# QCopterRC_KEY_Sch.net
KiCad netlist of a schematic drawn in Altium Designer
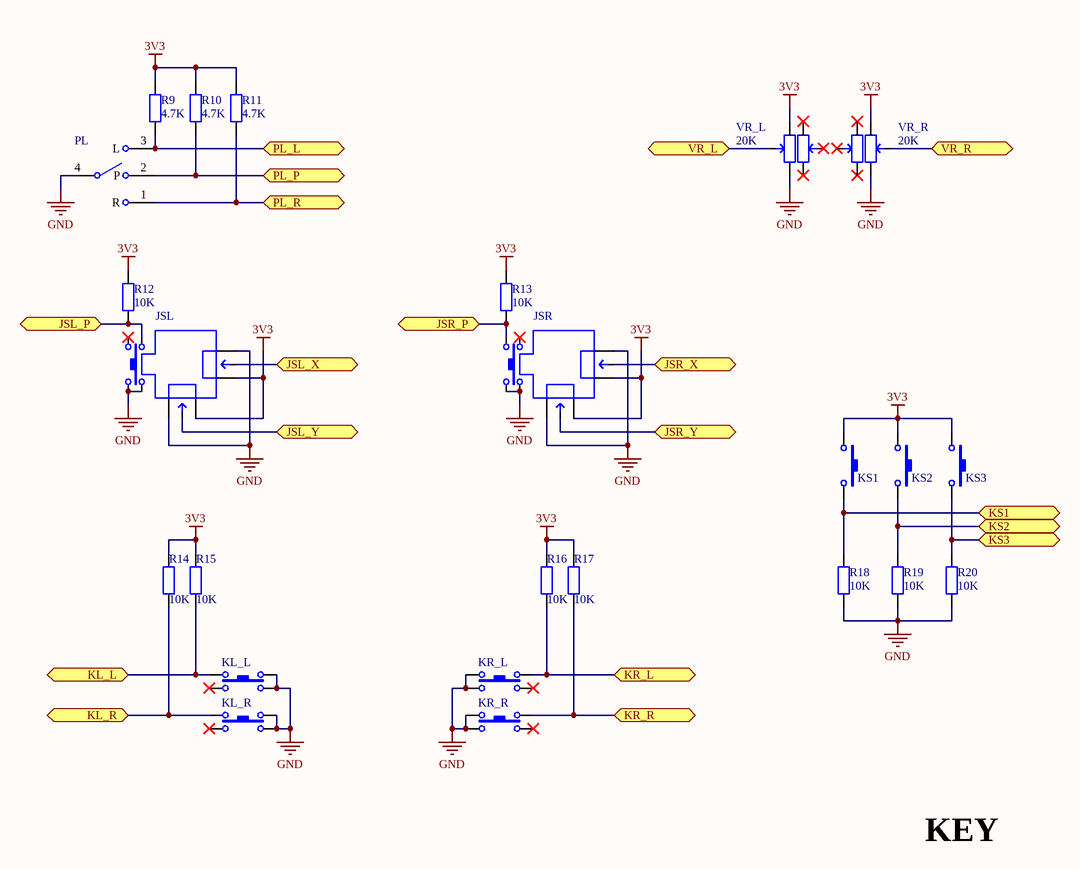
[diagram p0: QCopterRC_KEY_Sch.SchDoc]

(export (version "E")
  (design (tool "Eeschema 10.0.6"))
  (components
    (comp (ref "JSL")
      (value "JoyStick")
      (footprint "PCB_Switch:JoyStick")
      (libsource (lib "SCH_Switch") (part "JoyStick"))
    )
    (comp (ref "JSR")
      (value "JoyStick")
      (footprint "PCB_Switch:JoyStick")
      (libsource (lib "SCH_Switch") (part "JoyStick"))
    )
    (comp (ref "KL_L")
      (value "BT_TACT_12X12_D180")
      (footprint "PCB_Switch:BT_TACT_12X12_D180")
      (description "Switch")
      (libsource (lib "SCH_Switch") (part "BT_TACT_12X12_D180"))
    )
    (comp (ref "KL_R")
      (value "BT_TACT_12X12_D180")
      (footprint "PCB_Switch:BT_TACT_12X12_D180")
      (description "Switch")
      (libsource (lib "SCH_Switch") (part "BT_TACT_12X12_D180"))
    )
    (comp (ref "KR_L")
      (value "BT_TACT_12X12_D180")
      (footprint "PCB_Switch:BT_TACT_12X12_D180")
      (description "Switch")
      (libsource (lib "SCH_Switch") (part "BT_TACT_12X12_D180"))
    )
    (comp (ref "KR_R")
      (value "BT_TACT_12X12_D180")
      (footprint "PCB_Switch:BT_TACT_12X12_D180")
      (description "Switch")
      (libsource (lib "SCH_Switch") (part "BT_TACT_12X12_D180"))
    )
    (comp (ref "KS1")
      (value "BT_TACT_3x6_180")
      (footprint "PCB_Switch:BT_TACT_3x6_180")
      (description "Switch")
      (libsource (lib "SCH_Switch") (part "BT_TACT_3x6_180"))
    )
    (comp (ref "KS2")
      (value "BT_TACT_3x6_180")
      (footprint "PCB_Switch:BT_TACT_3x6_180")
      (description "Switch")
      (libsource (lib "SCH_Switch") (part "BT_TACT_3x6_180"))
    )
    (comp (ref "KS3")
      (value "BT_TACT_3x6_180")
      (footprint "PCB_Switch:BT_TACT_3x6_180")
      (description "Switch")
      (libsource (lib "SCH_Switch") (part "BT_TACT_3x6_180"))
    )
    (comp (ref "PL")
      (value "BT_PushLever_11*12_90")
      (footprint "PCB_Switch:BT_PushLever_11*12_90")
      (description "Switch")
      (libsource (lib "SCH_Switch") (part "BT_PushLever_11*12_90"))
    )
    (comp (ref "R9")
      (value "4.7K")
      (footprint "PCB_Passive:RES_0603")
      (description "Resistor")
      (fields (field (name "Comment") "Res_0603"))
      (libsource (lib "SCH_Passive") (part "Res_0603"))
    )
    (comp (ref "R10")
      (value "4.7K")
      (footprint "PCB_Passive:RES_0603")
      (description "Resistor")
      (fields (field (name "Comment") "Res_0603"))
      (libsource (lib "SCH_Passive") (part "Res_0603"))
    )
    (comp (ref "R11")
      (value "4.7K")
      (footprint "PCB_Passive:RES_0603")
      (description "Resistor")
      (fields (field (name "Comment") "Res_0603"))
      (libsource (lib "SCH_Passive") (part "Res_0603"))
    )
    (comp (ref "R12")
      (value "10K")
      (footprint "PCB_Passive:RES_0603")
      (description "Resistor")
      (fields (field (name "Comment") "Res_0603"))
      (libsource (lib "SCH_Passive") (part "Res_0603"))
    )
    (comp (ref "R13")
      (value "10K")
      (footprint "PCB_Passive:RES_0603")
      (description "Resistor")
      (fields (field (name "Comment") "Res_0603"))
      (libsource (lib "SCH_Passive") (part "Res_0603"))
    )
    (comp (ref "R14")
      (value "10K")
      (footprint "PCB_Passive:RES_0603")
      (description "Resistor")
      (fields (field (name "Comment") "Res_0603"))
      (libsource (lib "SCH_Passive") (part "Res_0603"))
    )
    (comp (ref "R15")
      (value "10K")
      (footprint "PCB_Passive:RES_0603")
      (description "Resistor")
      (fields (field (name "Comment") "Res_0603"))
      (libsource (lib "SCH_Passive") (part "Res_0603"))
    )
    (comp (ref "R16")
      (value "10K")
      (footprint "PCB_Passive:RES_0603")
      (description "Resistor")
      (fields (field (name "Comment") "Res_0603"))
      (libsource (lib "SCH_Passive") (part "Res_0603"))
    )
    (comp (ref "R17")
      (value "10K")
      (footprint "PCB_Passive:RES_0603")
      (description "Resistor")
      (fields (field (name "Comment") "Res_0603"))
      (libsource (lib "SCH_Passive") (part "Res_0603"))
    )
    (comp (ref "R18")
      (value "10K")
      (footprint "PCB_Passive:RES_0603")
      (description "Resistor")
      (fields (field (name "Comment") "Res_0603"))
      (libsource (lib "SCH_Passive") (part "Res_0603"))
    )
    (comp (ref "R19")
      (value "10K")
      (footprint "PCB_Passive:RES_0603")
      (description "Resistor")
      (fields (field (name "Comment") "Res_0603"))
      (libsource (lib "SCH_Passive") (part "Res_0603"))
    )
    (comp (ref "R20")
      (value "10K")
      (footprint "PCB_Passive:RES_0603")
      (description "Resistor")
      (fields (field (name "Comment") "Res_0603"))
      (libsource (lib "SCH_Passive") (part "Res_0603"))
    )
    (comp (ref "VR_L")
      (value "20K")
      (footprint "PCB_Passive:RES_45MM_DIP")
      (description "Resistor")
      (fields (field (name "Comment") "RES_45MM_DIP"))
      (libsource (lib "SCH_Passive") (part "RES_45MM_DIP"))
    )
    (comp (ref "VR_R")
      (value "20K")
      (footprint "PCB_Passive:RES_45MM_DIP")
      (description "Resistor")
      (fields (field (name "Comment") "RES_45MM_DIP"))
      (libsource (lib "SCH_Passive") (part "RES_45MM_DIP"))
    )
  )
  (nets
    (net (code "1") (name "/JSL_P") (class "Default")
      (node (ref "JSL") (pin "9") (pinfunction "9_9") (pintype "passive"))
      (node (ref "R12") (pin "2") (pinfunction "2_2") (pintype "passive"))
    )
    (net (code "2") (name "/JSL_X") (class "Default")
      (node (ref "JSL") (pin "5") (pinfunction "5_5") (pintype "passive"))
    )
    (net (code "3") (name "/JSL_Y") (class "Default")
      (node (ref "JSL") (pin "2") (pinfunction "2_2") (pintype "passive"))
    )
    (net (code "4") (name "/JSR_P") (class "Default")
      (node (ref "JSR") (pin "7") (pinfunction "7_7") (pintype "passive"))
      (node (ref "R13") (pin "2") (pinfunction "2_2") (pintype "passive"))
    )
    (net (code "5") (name "/JSR_X") (class "Default")
      (node (ref "JSR") (pin "5") (pinfunction "5_5") (pintype "passive"))
    )
    (net (code "6") (name "/JSR_Y") (class "Default")
      (node (ref "JSR") (pin "2") (pinfunction "2_2") (pintype "passive"))
    )
    (net (code "7") (name "/KL_L") (class "Default")
      (node (ref "KL_L") (pin "1") (pinfunction "1_1") (pintype "passive"))
      (node (ref "R15") (pin "2") (pinfunction "2_2") (pintype "passive"))
    )
    (net (code "8") (name "/KL_R") (class "Default")
      (node (ref "KL_R") (pin "1") (pinfunction "1_1") (pintype "passive"))
      (node (ref "R14") (pin "2") (pinfunction "2_2") (pintype "passive"))
    )
    (net (code "9") (name "/KR_L") (class "Default")
      (node (ref "KR_L") (pin "2") (pinfunction "2_2") (pintype "passive"))
      (node (ref "R16") (pin "2") (pinfunction "2_2") (pintype "passive"))
    )
    (net (code "10") (name "/KR_R") (class "Default")
      (node (ref "KR_R") (pin "2") (pinfunction "2_2") (pintype "passive"))
      (node (ref "R17") (pin "2") (pinfunction "2_2") (pintype "passive"))
    )
    (net (code "11") (name "/KS1") (class "Default")
      (node (ref "KS1") (pin "2") (pinfunction "2_2") (pintype "passive"))
      (node (ref "R18") (pin "1") (pinfunction "1_1") (pintype "passive"))
    )
    (net (code "12") (name "/KS2") (class "Default")
      (node (ref "KS2") (pin "2") (pinfunction "2_2") (pintype "passive"))
      (node (ref "R19") (pin "1") (pinfunction "1_1") (pintype "passive"))
    )
    (net (code "13") (name "/KS3") (class "Default")
      (node (ref "KS3") (pin "2") (pinfunction "2_2") (pintype "passive"))
      (node (ref "R20") (pin "1") (pinfunction "1_1") (pintype "passive"))
    )
    (net (code "14") (name "/PL_L") (class "Default")
      (node (ref "PL") (pin "3") (pinfunction "L_3") (pintype "passive"))
      (node (ref "R9") (pin "2") (pinfunction "2_2") (pintype "passive"))
    )
    (net (code "15") (name "/PL_P") (class "Default")
      (node (ref "PL") (pin "2") (pinfunction "P_2") (pintype "passive"))
      (node (ref "R10") (pin "2") (pinfunction "2_2") (pintype "passive"))
    )
    (net (code "16") (name "/PL_R") (class "Default")
      (node (ref "PL") (pin "1") (pinfunction "R_1") (pintype "passive"))
      (node (ref "R11") (pin "2") (pinfunction "2_2") (pintype "passive"))
    )
    (net (code "17") (name "/VR_L") (class "Default")
      (node (ref "VR_L") (pin "2") (pinfunction "W_2") (pintype "passive"))
    )
    (net (code "18") (name "/VR_R") (class "Default")
      (node (ref "VR_R") (pin "4") (pinfunction "W_4") (pintype "passive"))
    )
    (net (code "19") (name "3V3") (class "Default")
      (node (ref "JSL") (pin "3") (pinfunction "3_3") (pintype "passive"))
      (node (ref "JSL") (pin "4") (pinfunction "4_4") (pintype "passive"))
      (node (ref "JSR") (pin "3") (pinfunction "3_3") (pintype "passive"))
      (node (ref "JSR") (pin "4") (pinfunction "4_4") (pintype "passive"))
      (node (ref "KS1") (pin "1") (pinfunction "1_1") (pintype "passive"))
      (node (ref "KS2") (pin "1") (pinfunction "1_1") (pintype "passive"))
      (node (ref "KS3") (pin "1") (pinfunction "1_1") (pintype "passive"))
      (node (ref "R10") (pin "1") (pinfunction "1_1") (pintype "passive"))
      (node (ref "R11") (pin "1") (pinfunction "1_1") (pintype "passive"))
      (node (ref "R12") (pin "1") (pinfunction "1_1") (pintype "passive"))
      (node (ref "R13") (pin "1") (pinfunction "1_1") (pintype "passive"))
      (node (ref "R14") (pin "1") (pinfunction "1_1") (pintype "passive"))
      (node (ref "R15") (pin "1") (pinfunction "1_1") (pintype "passive"))
      (node (ref "R16") (pin "1") (pinfunction "1_1") (pintype "passive"))
      (node (ref "R17") (pin "1") (pinfunction "1_1") (pintype "passive"))
      (node (ref "R9") (pin "1") (pinfunction "1_1") (pintype "passive"))
      (node (ref "VR_L") (pin "1") (pinfunction "U_1") (pintype "passive"))
      (node (ref "VR_R") (pin "3") (pinfunction "U_3") (pintype "passive"))
    )
    (net (code "20") (name "GND") (class "Default")
      (node (ref "JSL") (pin "1") (pinfunction "1_1") (pintype "passive"))
      (node (ref "JSL") (pin "10") (pinfunction "10_10") (pintype "passive"))
      (node (ref "JSL") (pin "6") (pinfunction "6_6") (pintype "passive"))
      (node (ref "JSL") (pin "8") (pinfunction "8_8") (pintype "passive"))
      (node (ref "JSR") (pin "1") (pinfunction "1_1") (pintype "passive"))
      (node (ref "JSR") (pin "10") (pinfunction "10_10") (pintype "passive"))
      (node (ref "JSR") (pin "6") (pinfunction "6_6") (pintype "passive"))
      (node (ref "JSR") (pin "8") (pinfunction "8_8") (pintype "passive"))
      (node (ref "KL_L") (pin "2") (pinfunction "2_2") (pintype "passive"))
      (node (ref "KL_L") (pin "4") (pinfunction "4_4") (pintype "passive"))
      (node (ref "KL_R") (pin "2") (pinfunction "2_2") (pintype "passive"))
      (node (ref "KL_R") (pin "4") (pinfunction "4_4") (pintype "passive"))
      (node (ref "KR_L") (pin "1") (pinfunction "1_1") (pintype "passive"))
      (node (ref "KR_L") (pin "3") (pinfunction "3_3") (pintype "passive"))
      (node (ref "KR_R") (pin "1") (pinfunction "1_1") (pintype "passive"))
      (node (ref "KR_R") (pin "3") (pinfunction "3_3") (pintype "passive"))
      (node (ref "PL") (pin "4") (pinfunction "4_4") (pintype "passive"))
      (node (ref "R18") (pin "2") (pinfunction "2_2") (pintype "passive"))
      (node (ref "R19") (pin "2") (pinfunction "2_2") (pintype "passive"))
      (node (ref "R20") (pin "2") (pinfunction "2_2") (pintype "passive"))
      (node (ref "VR_L") (pin "5") (pinfunction "D_5") (pintype "passive"))
      (node (ref "VR_R") (pin "6") (pinfunction "D_6") (pintype "passive"))
    )
    (net (code "21") (name "unconnected-(JSL-Pad7)") (class "Default")
      (node (ref "JSL") (pin "7") (pinfunction "7_7") (pintype "passive+no_connect"))
    )
    (net (code "22") (name "unconnected-(JSR-Pad9)") (class "Default")
      (node (ref "JSR") (pin "9") (pinfunction "9_9") (pintype "passive+no_connect"))
    )
    (net (code "23") (name "unconnected-(KL_L-Pad3)") (class "Default")
      (node (ref "KL_L") (pin "3") (pinfunction "3_3") (pintype "passive+no_connect"))
    )
    (net (code "24") (name "unconnected-(KL_R-Pad3)") (class "Default")
      (node (ref "KL_R") (pin "3") (pinfunction "3_3") (pintype "passive+no_connect"))
    )
    (net (code "25") (name "unconnected-(KR_L-Pad4)") (class "Default")
      (node (ref "KR_L") (pin "4") (pinfunction "4_4") (pintype "passive+no_connect"))
    )
    (net (code "26") (name "unconnected-(KR_R-Pad4)") (class "Default")
      (node (ref "KR_R") (pin "4") (pinfunction "4_4") (pintype "passive+no_connect"))
    )
    (net (code "27") (name "unconnected-(VR_L-D-Pad6)") (class "Default")
      (node (ref "VR_L") (pin "6") (pinfunction "D_6") (pintype "passive+no_connect"))
    )
    (net (code "28") (name "unconnected-(VR_L-U-Pad3)") (class "Default")
      (node (ref "VR_L") (pin "3") (pinfunction "U_3") (pintype "passive+no_connect"))
    )
    (net (code "29") (name "unconnected-(VR_L-W-Pad4)") (class "Default")
      (node (ref "VR_L") (pin "4") (pinfunction "W_4") (pintype "passive+no_connect"))
    )
    (net (code "30") (name "unconnected-(VR_R-D-Pad5)") (class "Default")
      (node (ref "VR_R") (pin "5") (pinfunction "D_5") (pintype "passive+no_connect"))
    )
    (net (code "31") (name "unconnected-(VR_R-U-Pad1)") (class "Default")
      (node (ref "VR_R") (pin "1") (pinfunction "U_1") (pintype "passive+no_connect"))
    )
    (net (code "32") (name "unconnected-(VR_R-W-Pad2)") (class "Default")
      (node (ref "VR_R") (pin "2") (pinfunction "W_2") (pintype "passive+no_connect"))
    )
  )
)
